# schematic_mod.net
KiCad netlist of a schematic drawn in EAGLE
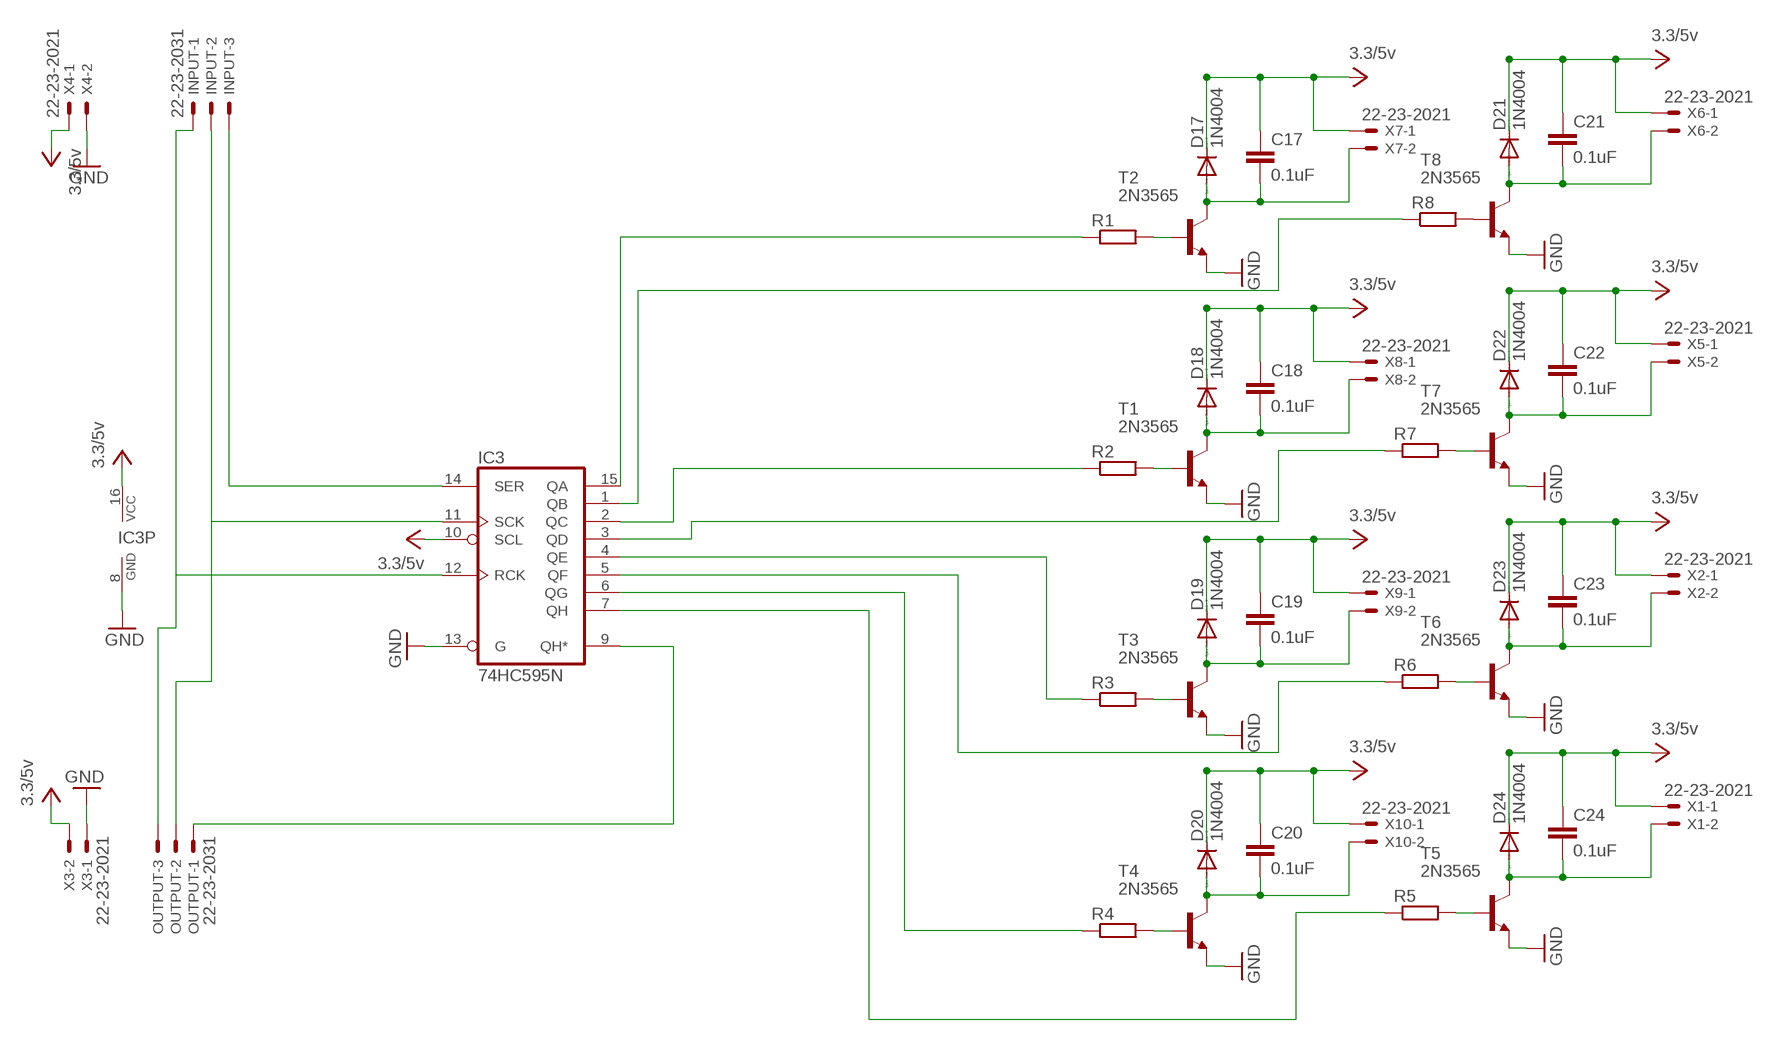
[diagram p0: schematic, sheet 1]

(export (version "E")
  (design (tool "Eeschema 10.0.6"))
  (components
    (comp (ref "C17")
      (value "0.1uF")
      (footprint "eagle-import:C025-024X044")
      (libsource (lib "eagle-import") (part "C-EU025-024X044"))
    )
    (comp (ref "C18")
      (value "0.1uF")
      (footprint "eagle-import:C025-024X044")
      (libsource (lib "eagle-import") (part "C-EU025-024X044"))
    )
    (comp (ref "C19")
      (value "0.1uF")
      (footprint "eagle-import:C025-024X044")
      (libsource (lib "eagle-import") (part "C-EU025-024X044"))
    )
    (comp (ref "C20")
      (value "0.1uF")
      (footprint "eagle-import:C025-024X044")
      (libsource (lib "eagle-import") (part "C-EU025-024X044"))
    )
    (comp (ref "C21")
      (value "0.1uF")
      (footprint "eagle-import:C025-024X044")
      (libsource (lib "eagle-import") (part "C-EU025-024X044"))
    )
    (comp (ref "C22")
      (value "0.1uF")
      (footprint "eagle-import:C025-024X044")
      (libsource (lib "eagle-import") (part "C-EU025-024X044"))
    )
    (comp (ref "C23")
      (value "0.1uF")
      (footprint "eagle-import:C025-024X044")
      (libsource (lib "eagle-import") (part "C-EU025-024X044"))
    )
    (comp (ref "C24")
      (value "0.1uF")
      (footprint "eagle-import:C025-024X044")
      (libsource (lib "eagle-import") (part "C-EU025-024X044"))
    )
    (comp (ref "D17")
      (value "1N4004")
      (footprint "eagle-import:DO41-10")
      (libsource (lib "eagle-import") (part "1N4004"))
    )
    (comp (ref "D18")
      (value "1N4004")
      (footprint "eagle-import:DO41-10")
      (libsource (lib "eagle-import") (part "1N4004"))
    )
    (comp (ref "D19")
      (value "1N4004")
      (footprint "eagle-import:DO41-10")
      (libsource (lib "eagle-import") (part "1N4004"))
    )
    (comp (ref "D20")
      (value "1N4004")
      (footprint "eagle-import:DO41-10")
      (libsource (lib "eagle-import") (part "1N4004"))
    )
    (comp (ref "D21")
      (value "1N4004")
      (footprint "eagle-import:DO41-10")
      (libsource (lib "eagle-import") (part "1N4004"))
    )
    (comp (ref "D22")
      (value "1N4004")
      (footprint "eagle-import:DO41-10")
      (libsource (lib "eagle-import") (part "1N4004"))
    )
    (comp (ref "D23")
      (value "1N4004")
      (footprint "eagle-import:DO41-10")
      (libsource (lib "eagle-import") (part "1N4004"))
    )
    (comp (ref "D24")
      (value "1N4004")
      (footprint "eagle-import:DO41-10")
      (libsource (lib "eagle-import") (part "1N4004"))
    )
    (comp (ref "IC3")
      (value "74HC595N")
      (footprint "eagle-import:DIL16")
      (libsource (lib "eagle-import") (part "74595NHC"))
    )
    (comp (ref "INPUT")
      (value "22-23-2031")
      (footprint "eagle-import:22-23-2031")
      (fields (field (name "MF") "MOLEX"))
      (libsource (lib "eagle-import") (part "22-23-2031"))
    )
    (comp (ref "OUTPUT")
      (value "22-23-2031")
      (footprint "eagle-import:22-23-2031")
      (fields (field (name "MF") "MOLEX"))
      (libsource (lib "eagle-import") (part "22-23-2031"))
    )
    (comp (ref "R1")
      (value "R-EU_0207/7")
      (footprint "eagle-import:0207_7")
      (libsource (lib "eagle-import") (part "R-EU_0207/7"))
    )
    (comp (ref "R2")
      (value "R-EU_0207/7")
      (footprint "eagle-import:0207_7")
      (libsource (lib "eagle-import") (part "R-EU_0207/7"))
    )
    (comp (ref "R3")
      (value "R-EU_0207/7")
      (footprint "eagle-import:0207_7")
      (libsource (lib "eagle-import") (part "R-EU_0207/7"))
    )
    (comp (ref "R4")
      (value "R-EU_0207/7")
      (footprint "eagle-import:0207_7")
      (libsource (lib "eagle-import") (part "R-EU_0207/7"))
    )
    (comp (ref "R5")
      (value "R-EU_0207/7")
      (footprint "eagle-import:0207_7")
      (libsource (lib "eagle-import") (part "R-EU_0207/7"))
    )
    (comp (ref "R6")
      (value "R-EU_0207/7")
      (footprint "eagle-import:0207_7")
      (libsource (lib "eagle-import") (part "R-EU_0207/7"))
    )
    (comp (ref "R7")
      (value "R-EU_0207/7")
      (footprint "eagle-import:0207_7")
      (libsource (lib "eagle-import") (part "R-EU_0207/7"))
    )
    (comp (ref "R8")
      (value "R-EU_0207/7")
      (footprint "eagle-import:0207_7")
      (libsource (lib "eagle-import") (part "R-EU_0207/7"))
    )
    (comp (ref "T1")
      (value "2N3565")
      (footprint "eagle-import:TO92")
      (libsource (lib "eagle-import") (part "2N3565"))
    )
    (comp (ref "T2")
      (value "2N3565")
      (footprint "eagle-import:TO92")
      (libsource (lib "eagle-import") (part "2N3565"))
    )
    (comp (ref "T3")
      (value "2N3565")
      (footprint "eagle-import:TO92")
      (libsource (lib "eagle-import") (part "2N3565"))
    )
    (comp (ref "T4")
      (value "2N3565")
      (footprint "eagle-import:TO92")
      (libsource (lib "eagle-import") (part "2N3565"))
    )
    (comp (ref "T5")
      (value "2N3565")
      (footprint "eagle-import:TO92")
      (libsource (lib "eagle-import") (part "2N3565"))
    )
    (comp (ref "T6")
      (value "2N3565")
      (footprint "eagle-import:TO92")
      (libsource (lib "eagle-import") (part "2N3565"))
    )
    (comp (ref "T7")
      (value "2N3565")
      (footprint "eagle-import:TO92")
      (libsource (lib "eagle-import") (part "2N3565"))
    )
    (comp (ref "T8")
      (value "2N3565")
      (footprint "eagle-import:TO92")
      (libsource (lib "eagle-import") (part "2N3565"))
    )
    (comp (ref "X1")
      (value "22-23-2021")
      (footprint "eagle-import:22-23-2021")
      (fields (field (name "MF") "MOLEX"))
      (libsource (lib "eagle-import") (part "22-23-2021"))
    )
    (comp (ref "X2")
      (value "22-23-2021")
      (footprint "eagle-import:22-23-2021")
      (fields (field (name "MF") "MOLEX"))
      (libsource (lib "eagle-import") (part "22-23-2021"))
    )
    (comp (ref "X3")
      (value "22-23-2021")
      (footprint "eagle-import:22-23-2021")
      (fields (field (name "MF") "MOLEX"))
      (libsource (lib "eagle-import") (part "22-23-2021"))
    )
    (comp (ref "X4")
      (value "22-23-2021")
      (footprint "eagle-import:22-23-2021")
      (fields (field (name "MF") "MOLEX"))
      (libsource (lib "eagle-import") (part "22-23-2021"))
    )
    (comp (ref "X5")
      (value "22-23-2021")
      (footprint "eagle-import:22-23-2021")
      (fields (field (name "MF") "MOLEX"))
      (libsource (lib "eagle-import") (part "22-23-2021"))
    )
    (comp (ref "X6")
      (value "22-23-2021")
      (footprint "eagle-import:22-23-2021")
      (fields (field (name "MF") "MOLEX"))
      (libsource (lib "eagle-import") (part "22-23-2021"))
    )
    (comp (ref "X7")
      (value "22-23-2021")
      (footprint "eagle-import:22-23-2021")
      (fields (field (name "MF") "MOLEX"))
      (libsource (lib "eagle-import") (part "22-23-2021"))
    )
    (comp (ref "X8")
      (value "22-23-2021")
      (footprint "eagle-import:22-23-2021")
      (fields (field (name "MF") "MOLEX"))
      (libsource (lib "eagle-import") (part "22-23-2021"))
    )
    (comp (ref "X9")
      (value "22-23-2021")
      (footprint "eagle-import:22-23-2021")
      (fields (field (name "MF") "MOLEX"))
      (libsource (lib "eagle-import") (part "22-23-2021"))
    )
    (comp (ref "X10")
      (value "22-23-2021")
      (footprint "eagle-import:22-23-2021")
      (fields (field (name "MF") "MOLEX"))
      (libsource (lib "eagle-import") (part "22-23-2021"))
    )
  )
  (nets
    (net (code "1") (name "3.3{slash}5v") (class "Default")
      (node (ref "C17") (pin "1") (pinfunction "1_1") (pintype "passive"))
      (node (ref "C18") (pin "1") (pinfunction "1_1") (pintype "passive"))
      (node (ref "C19") (pin "1") (pinfunction "1_1") (pintype "passive"))
      (node (ref "C20") (pin "1") (pinfunction "1_1") (pintype "passive"))
      (node (ref "C21") (pin "1") (pinfunction "1_1") (pintype "passive"))
      (node (ref "C22") (pin "1") (pinfunction "1_1") (pintype "passive"))
      (node (ref "C23") (pin "1") (pinfunction "1_1") (pintype "passive"))
      (node (ref "C24") (pin "1") (pinfunction "1_1") (pintype "passive"))
      (node (ref "D17") (pin "C") (pinfunction "C_C") (pintype "passive"))
      (node (ref "D18") (pin "C") (pinfunction "C_C") (pintype "passive"))
      (node (ref "D19") (pin "C") (pinfunction "C_C") (pintype "passive"))
      (node (ref "D20") (pin "C") (pinfunction "C_C") (pintype "passive"))
      (node (ref "D21") (pin "C") (pinfunction "C_C") (pintype "passive"))
      (node (ref "D22") (pin "C") (pinfunction "C_C") (pintype "passive"))
      (node (ref "D23") (pin "C") (pinfunction "C_C") (pintype "passive"))
      (node (ref "D24") (pin "C") (pinfunction "C_C") (pintype "passive"))
      (node (ref "IC3") (pin "10") (pinfunction "SCL_10") (pintype "input"))
      (node (ref "IC3") (pin "16") (pinfunction "VCC_16") (pintype "power_in"))
      (node (ref "X1") (pin "1") (pinfunction "S_1") (pintype "passive"))
      (node (ref "X10") (pin "1") (pinfunction "S_1") (pintype "passive"))
      (node (ref "X2") (pin "1") (pinfunction "S_1") (pintype "passive"))
      (node (ref "X3") (pin "2") (pinfunction "S_2") (pintype "passive"))
      (node (ref "X4") (pin "1") (pinfunction "S_1") (pintype "passive"))
      (node (ref "X5") (pin "1") (pinfunction "S_1") (pintype "passive"))
      (node (ref "X6") (pin "1") (pinfunction "S_1") (pintype "passive"))
      (node (ref "X7") (pin "1") (pinfunction "S_1") (pintype "passive"))
      (node (ref "X8") (pin "1") (pinfunction "S_1") (pintype "passive"))
      (node (ref "X9") (pin "1") (pinfunction "S_1") (pintype "passive"))
    )
    (net (code "2") (name "GND") (class "Default")
      (node (ref "IC3") (pin "13") (pinfunction "G_13") (pintype "input"))
      (node (ref "IC3") (pin "8") (pinfunction "GND_8") (pintype "power_in"))
      (node (ref "T1") (pin "3") (pinfunction "E_3") (pintype "passive"))
      (node (ref "T2") (pin "3") (pinfunction "E_3") (pintype "passive"))
      (node (ref "T3") (pin "3") (pinfunction "E_3") (pintype "passive"))
      (node (ref "T4") (pin "3") (pinfunction "E_3") (pintype "passive"))
      (node (ref "T5") (pin "3") (pinfunction "E_3") (pintype "passive"))
      (node (ref "T6") (pin "3") (pinfunction "E_3") (pintype "passive"))
      (node (ref "T7") (pin "3") (pinfunction "E_3") (pintype "passive"))
      (node (ref "T8") (pin "3") (pinfunction "E_3") (pintype "passive"))
      (node (ref "X3") (pin "1") (pinfunction "S_1") (pintype "passive"))
      (node (ref "X4") (pin "2") (pinfunction "S_2") (pintype "passive"))
    )
    (net (code "3") (name "Net-(IC3A-QA)") (class "Default")
      (node (ref "IC3") (pin "15") (pinfunction "QA_15") (pintype "tri_state"))
      (node (ref "R1") (pin "1") (pinfunction "1_1") (pintype "passive"))
    )
    (net (code "4") (name "Net-(IC3A-QB)") (class "Default")
      (node (ref "IC3") (pin "1") (pinfunction "QB_1") (pintype "tri_state"))
      (node (ref "R8") (pin "1") (pinfunction "1_1") (pintype "passive"))
    )
    (net (code "5") (name "Net-(IC3A-QC)") (class "Default")
      (node (ref "IC3") (pin "2") (pinfunction "QC_2") (pintype "tri_state"))
      (node (ref "R2") (pin "1") (pinfunction "1_1") (pintype "passive"))
    )
    (net (code "6") (name "Net-(IC3A-QD)") (class "Default")
      (node (ref "IC3") (pin "3") (pinfunction "QD_3") (pintype "tri_state"))
      (node (ref "R7") (pin "1") (pinfunction "1_1") (pintype "passive"))
    )
    (net (code "7") (name "Net-(IC3A-QE)") (class "Default")
      (node (ref "IC3") (pin "4") (pinfunction "QE_4") (pintype "tri_state"))
      (node (ref "R3") (pin "1") (pinfunction "1_1") (pintype "passive"))
    )
    (net (code "8") (name "Net-(IC3A-QF)") (class "Default")
      (node (ref "IC3") (pin "5") (pinfunction "QF_5") (pintype "tri_state"))
      (node (ref "R6") (pin "1") (pinfunction "1_1") (pintype "passive"))
    )
    (net (code "9") (name "Net-(IC3A-QG)") (class "Default")
      (node (ref "IC3") (pin "6") (pinfunction "QG_6") (pintype "tri_state"))
      (node (ref "R4") (pin "1") (pinfunction "1_1") (pintype "passive"))
    )
    (net (code "10") (name "Net-(IC3A-QH)") (class "Default")
      (node (ref "IC3") (pin "7") (pinfunction "QH_7") (pintype "tri_state"))
      (node (ref "R5") (pin "1") (pinfunction "1_1") (pintype "passive"))
    )
    (net (code "11") (name "Net-(IC3A-QH*)") (class "Default")
      (node (ref "IC3") (pin "9") (pinfunction "QH*_9") (pintype "tri_state"))
      (node (ref "OUTPUT") (pin "1") (pinfunction "S_1") (pintype "passive"))
    )
    (net (code "12") (name "Net-(IC3A-RCK)") (class "Default")
      (node (ref "IC3") (pin "12") (pinfunction "RCK_12") (pintype "input"))
      (node (ref "INPUT") (pin "1") (pinfunction "S_1") (pintype "passive"))
      (node (ref "OUTPUT") (pin "3") (pinfunction "S_3") (pintype "passive"))
    )
    (net (code "13") (name "Net-(IC3A-SCK)") (class "Default")
      (node (ref "IC3") (pin "11") (pinfunction "SCK_11") (pintype "input"))
      (node (ref "INPUT") (pin "2") (pinfunction "S_2") (pintype "passive"))
      (node (ref "OUTPUT") (pin "2") (pinfunction "S_2") (pintype "passive"))
    )
    (net (code "14") (name "Net-(IC3A-SER)") (class "Default")
      (node (ref "IC3") (pin "14") (pinfunction "SER_14") (pintype "input"))
      (node (ref "INPUT") (pin "3") (pinfunction "S_3") (pintype "passive"))
    )
    (net (code "15") (name "Net-(T1-B)") (class "Default")
      (node (ref "R2") (pin "2") (pinfunction "2_2") (pintype "passive"))
      (node (ref "T1") (pin "2") (pinfunction "B_2") (pintype "passive"))
    )
    (net (code "16") (name "Net-(T1-C)") (class "Default")
      (node (ref "C18") (pin "2") (pinfunction "2_2") (pintype "passive"))
      (node (ref "D18") (pin "A") (pinfunction "A_A") (pintype "passive"))
      (node (ref "T1") (pin "1") (pinfunction "C_1") (pintype "passive"))
      (node (ref "X8") (pin "2") (pinfunction "S_2") (pintype "passive"))
    )
    (net (code "17") (name "Net-(T2-B)") (class "Default")
      (node (ref "R1") (pin "2") (pinfunction "2_2") (pintype "passive"))
      (node (ref "T2") (pin "2") (pinfunction "B_2") (pintype "passive"))
    )
    (net (code "18") (name "Net-(T2-C)") (class "Default")
      (node (ref "C17") (pin "2") (pinfunction "2_2") (pintype "passive"))
      (node (ref "D17") (pin "A") (pinfunction "A_A") (pintype "passive"))
      (node (ref "T2") (pin "1") (pinfunction "C_1") (pintype "passive"))
      (node (ref "X7") (pin "2") (pinfunction "S_2") (pintype "passive"))
    )
    (net (code "19") (name "Net-(T3-B)") (class "Default")
      (node (ref "R3") (pin "2") (pinfunction "2_2") (pintype "passive"))
      (node (ref "T3") (pin "2") (pinfunction "B_2") (pintype "passive"))
    )
    (net (code "20") (name "Net-(T3-C)") (class "Default")
      (node (ref "C19") (pin "2") (pinfunction "2_2") (pintype "passive"))
      (node (ref "D19") (pin "A") (pinfunction "A_A") (pintype "passive"))
      (node (ref "T3") (pin "1") (pinfunction "C_1") (pintype "passive"))
      (node (ref "X9") (pin "2") (pinfunction "S_2") (pintype "passive"))
    )
    (net (code "21") (name "Net-(T4-B)") (class "Default")
      (node (ref "R4") (pin "2") (pinfunction "2_2") (pintype "passive"))
      (node (ref "T4") (pin "2") (pinfunction "B_2") (pintype "passive"))
    )
    (net (code "22") (name "Net-(T4-C)") (class "Default")
      (node (ref "C20") (pin "2") (pinfunction "2_2") (pintype "passive"))
      (node (ref "D20") (pin "A") (pinfunction "A_A") (pintype "passive"))
      (node (ref "T4") (pin "1") (pinfunction "C_1") (pintype "passive"))
      (node (ref "X10") (pin "2") (pinfunction "S_2") (pintype "passive"))
    )
    (net (code "23") (name "Net-(T5-B)") (class "Default")
      (node (ref "R5") (pin "2") (pinfunction "2_2") (pintype "passive"))
      (node (ref "T5") (pin "2") (pinfunction "B_2") (pintype "passive"))
    )
    (net (code "24") (name "Net-(T5-C)") (class "Default")
      (node (ref "C24") (pin "2") (pinfunction "2_2") (pintype "passive"))
      (node (ref "D24") (pin "A") (pinfunction "A_A") (pintype "passive"))
      (node (ref "T5") (pin "1") (pinfunction "C_1") (pintype "passive"))
      (node (ref "X1") (pin "2") (pinfunction "S_2") (pintype "passive"))
    )
    (net (code "25") (name "Net-(T6-B)") (class "Default")
      (node (ref "R6") (pin "2") (pinfunction "2_2") (pintype "passive"))
      (node (ref "T6") (pin "2") (pinfunction "B_2") (pintype "passive"))
    )
    (net (code "26") (name "Net-(T6-C)") (class "Default")
      (node (ref "C23") (pin "2") (pinfunction "2_2") (pintype "passive"))
      (node (ref "D23") (pin "A") (pinfunction "A_A") (pintype "passive"))
      (node (ref "T6") (pin "1") (pinfunction "C_1") (pintype "passive"))
      (node (ref "X2") (pin "2") (pinfunction "S_2") (pintype "passive"))
    )
    (net (code "27") (name "Net-(T7-B)") (class "Default")
      (node (ref "R7") (pin "2") (pinfunction "2_2") (pintype "passive"))
      (node (ref "T7") (pin "2") (pinfunction "B_2") (pintype "passive"))
    )
    (net (code "28") (name "Net-(T7-C)") (class "Default")
      (node (ref "C22") (pin "2") (pinfunction "2_2") (pintype "passive"))
      (node (ref "D22") (pin "A") (pinfunction "A_A") (pintype "passive"))
      (node (ref "T7") (pin "1") (pinfunction "C_1") (pintype "passive"))
      (node (ref "X5") (pin "2") (pinfunction "S_2") (pintype "passive"))
    )
    (net (code "29") (name "Net-(T8-B)") (class "Default")
      (node (ref "R8") (pin "2") (pinfunction "2_2") (pintype "passive"))
      (node (ref "T8") (pin "2") (pinfunction "B_2") (pintype "passive"))
    )
    (net (code "30") (name "Net-(T8-C)") (class "Default")
      (node (ref "C21") (pin "2") (pinfunction "2_2") (pintype "passive"))
      (node (ref "D21") (pin "A") (pinfunction "A_A") (pintype "passive"))
      (node (ref "T8") (pin "1") (pinfunction "C_1") (pintype "passive"))
      (node (ref "X6") (pin "2") (pinfunction "S_2") (pintype "passive"))
    )
  )
)
